# 3V3_REG.net
KiCad netlist of a schematic drawn in Altium Designer
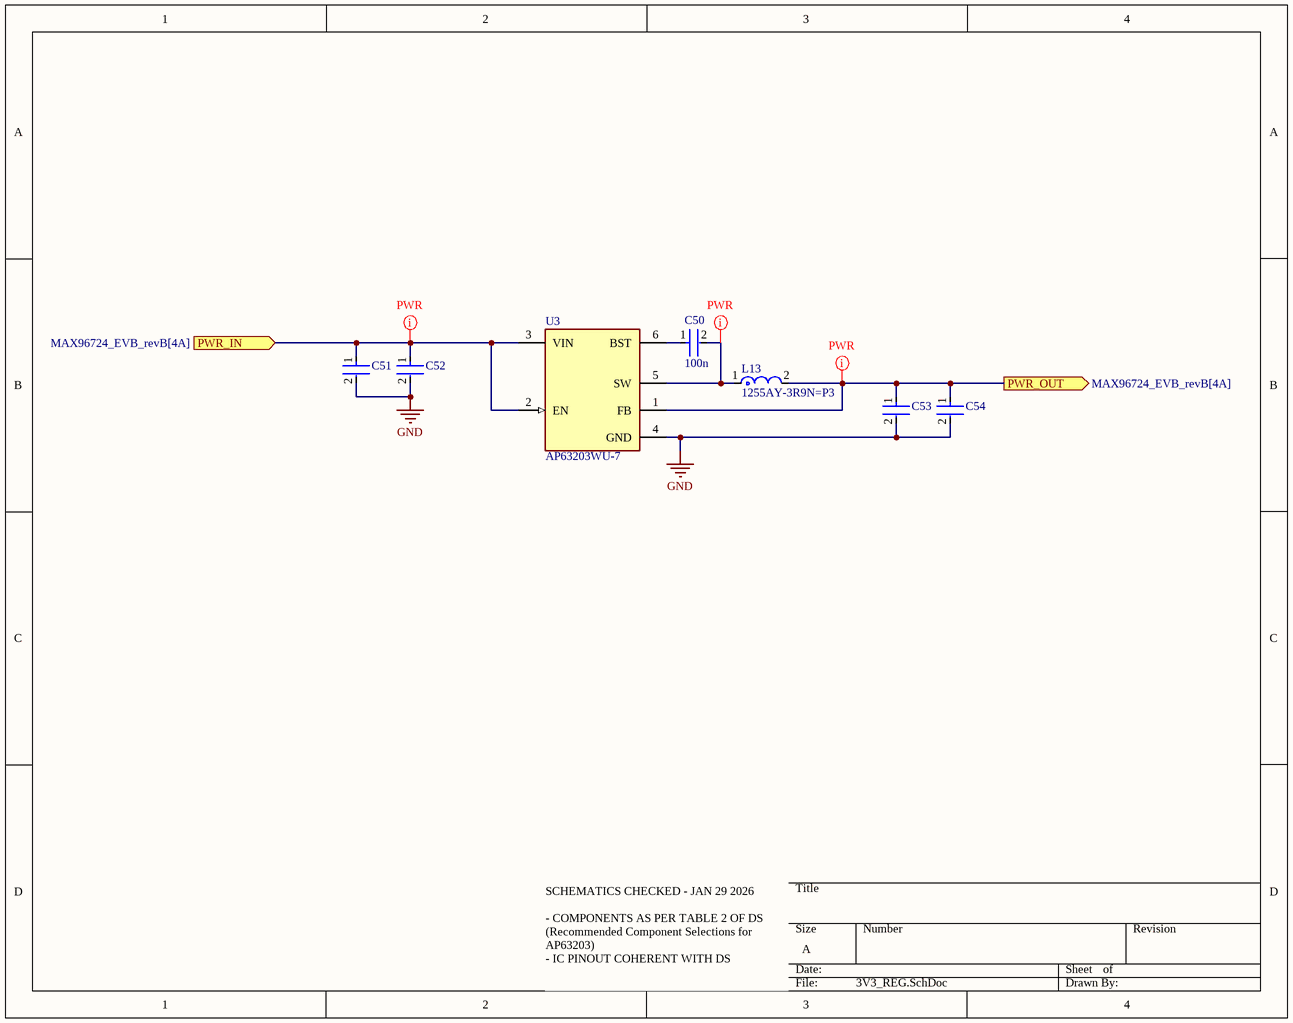
[diagram p0: 3V3_REG.SchDoc]

(export (version "E")
  (design (tool "Eeschema 10.0.6"))
  (components
    (comp (ref "C50")
      (value "100n")
      (footprint "FP-0402-L_1_0_0_05-W_0_5-IPC_A")
      (description "LARGE PADS, 0402 CAP, CHANGE COMMENT TO MATCH REAL P/N")
      (libsource (lib "Space Concordia") (part "b4654b650e69147ec39a6b967a45e02"))
    )
    (comp (ref "C51")
      (value "12103D106KAT2A")
      (footprint "FP-1210-L_3_3_0_4-W_2_5_0-MFG")
      (description "General Purpose Ceramic Capacitor, 1210, 10uF, 10%, X5R, 15%, 25V")
      (fields (field (name "VOLTAGE") "25V") (field (name "TOLERANCE") "10%"))
      (libsource (lib "Altium Content Vault") (part "b4654b650e69147ec39a6b967a45e02"))
    )
    (comp (ref "C52")
      (value "DNP")
      (footprint "FP-1210-L_3_3_0_4-W_2_5_0-MFG")
      (description "General Purpose Ceramic Capacitor, 1210, 10uF, 10%, X5R, 15%, 25V")
      (fields (field (name "VOLTAGE") "25V") (field (name "TOLERANCE") "10%"))
      (libsource (lib "Altium Content Vault") (part "b4654b650e69147ec39a6b967a45e02"))
    )
    (comp (ref "C53")
      (value "GRM21BR61E226ME44L")
      (footprint "FP-GRM21B-0_2-e0_2_0_7-IPC_B")
      (description "Chip Multilayer Ceramic Capacitors for General Purpose, 0805, 22uF, X5R, 15%, 20%, 25V")
      (fields (field (name "TOLERANCE") "20%") (field (name "VOLTAGE") "25V"))
      (libsource (lib "Altium Content Vault") (part "b4654b650e69147ec39a6b967a45e02"))
    )
    (comp (ref "C54")
      (value "GRM21BR61E226ME44L")
      (footprint "FP-GRM21B-0_2-e0_2_0_7-IPC_B")
      (description "Chip Multilayer Ceramic Capacitors for General Purpose, 0805, 22uF, X5R, 15%, 20%, 25V")
      (fields (field (name "TOLERANCE") "20%") (field (name "VOLTAGE") "25V"))
      (libsource (lib "Altium Content Vault") (part "b4654b650e69147ec39a6b967a45e02"))
    )
    (comp (ref "L13")
      (value "1255AY-3R9N=P3")
      (footprint "FP-DG6045C-MFG")
      (description "Shielded Wirewound Inductor 3.9uH 30% 4200mA 0.0264Ω SMD")
      (fields (field (name "TOLERANCE") "30%"))
      (libsource (lib "Altium Content Vault") (part "4cc4b267dca4c8e51f7102f422741d8"))
    )
    (comp (ref "U3")
      (value "AP63203WU-7")
      (footprint "FP-TSOT26-MFG")
      (description "IC REG BUCK 3.3V 2A TSOT26")
      (fields
        (field (name "MANUFACTURER") "Diodes Inc.")
        (field (name "OCTOPART") "https://octopart.com/ap63203wu-7-diodes+inc.-98099550")
      )
      (libsource (lib "Altium Content Vault") (part "0e61c2974d7114b43f01ef96ae2e524"))
    )
  )
  (nets
    (net (code "1") (name "/PWR_IN") (class "Default")
      (node (ref "C51") (pin "1") (pinfunction "1_1") (pintype "passive"))
      (node (ref "C52") (pin "1") (pinfunction "1_1") (pintype "passive"))
      (node (ref "U3") (pin "2") (pinfunction "EN_2") (pintype "input"))
      (node (ref "U3") (pin "3") (pinfunction "VIN_3") (pintype "power_in"))
    )
    (net (code "2") (name "/PWR_OUT") (class "Default")
      (node (ref "C53") (pin "1") (pinfunction "1_1") (pintype "passive"))
      (node (ref "C54") (pin "1") (pinfunction "1_1") (pintype "passive"))
      (node (ref "L13") (pin "2") (pinfunction "2_2") (pintype "passive"))
      (node (ref "U3") (pin "1") (pinfunction "FB_1") (pintype "passive"))
    )
    (net (code "3") (name "GND") (class "Default")
      (node (ref "C51") (pin "2") (pinfunction "2_2") (pintype "passive"))
      (node (ref "C52") (pin "2") (pinfunction "2_2") (pintype "passive"))
      (node (ref "C53") (pin "2") (pinfunction "2_2") (pintype "passive"))
      (node (ref "C54") (pin "2") (pinfunction "2_2") (pintype "passive"))
      (node (ref "U3") (pin "4") (pinfunction "GND_4") (pintype "power_in"))
    )
    (net (code "4") (name "Net-(U3-BST)") (class "Default")
      (node (ref "C50") (pin "1") (pinfunction "1_1") (pintype "passive"))
      (node (ref "U3") (pin "6") (pinfunction "BST_6") (pintype "passive"))
    )
    (net (code "5") (name "Net-(U3-SW)") (class "Default")
      (node (ref "C50") (pin "2") (pinfunction "2_2") (pintype "passive"))
      (node (ref "L13") (pin "1") (pinfunction "1_1") (pintype "passive"))
      (node (ref "U3") (pin "5") (pinfunction "SW_5") (pintype "passive"))
    )
  )
)
